# Mergen_Ground_Station_V2_0.net
KiCad netlist of a schematic drawn in EAGLE
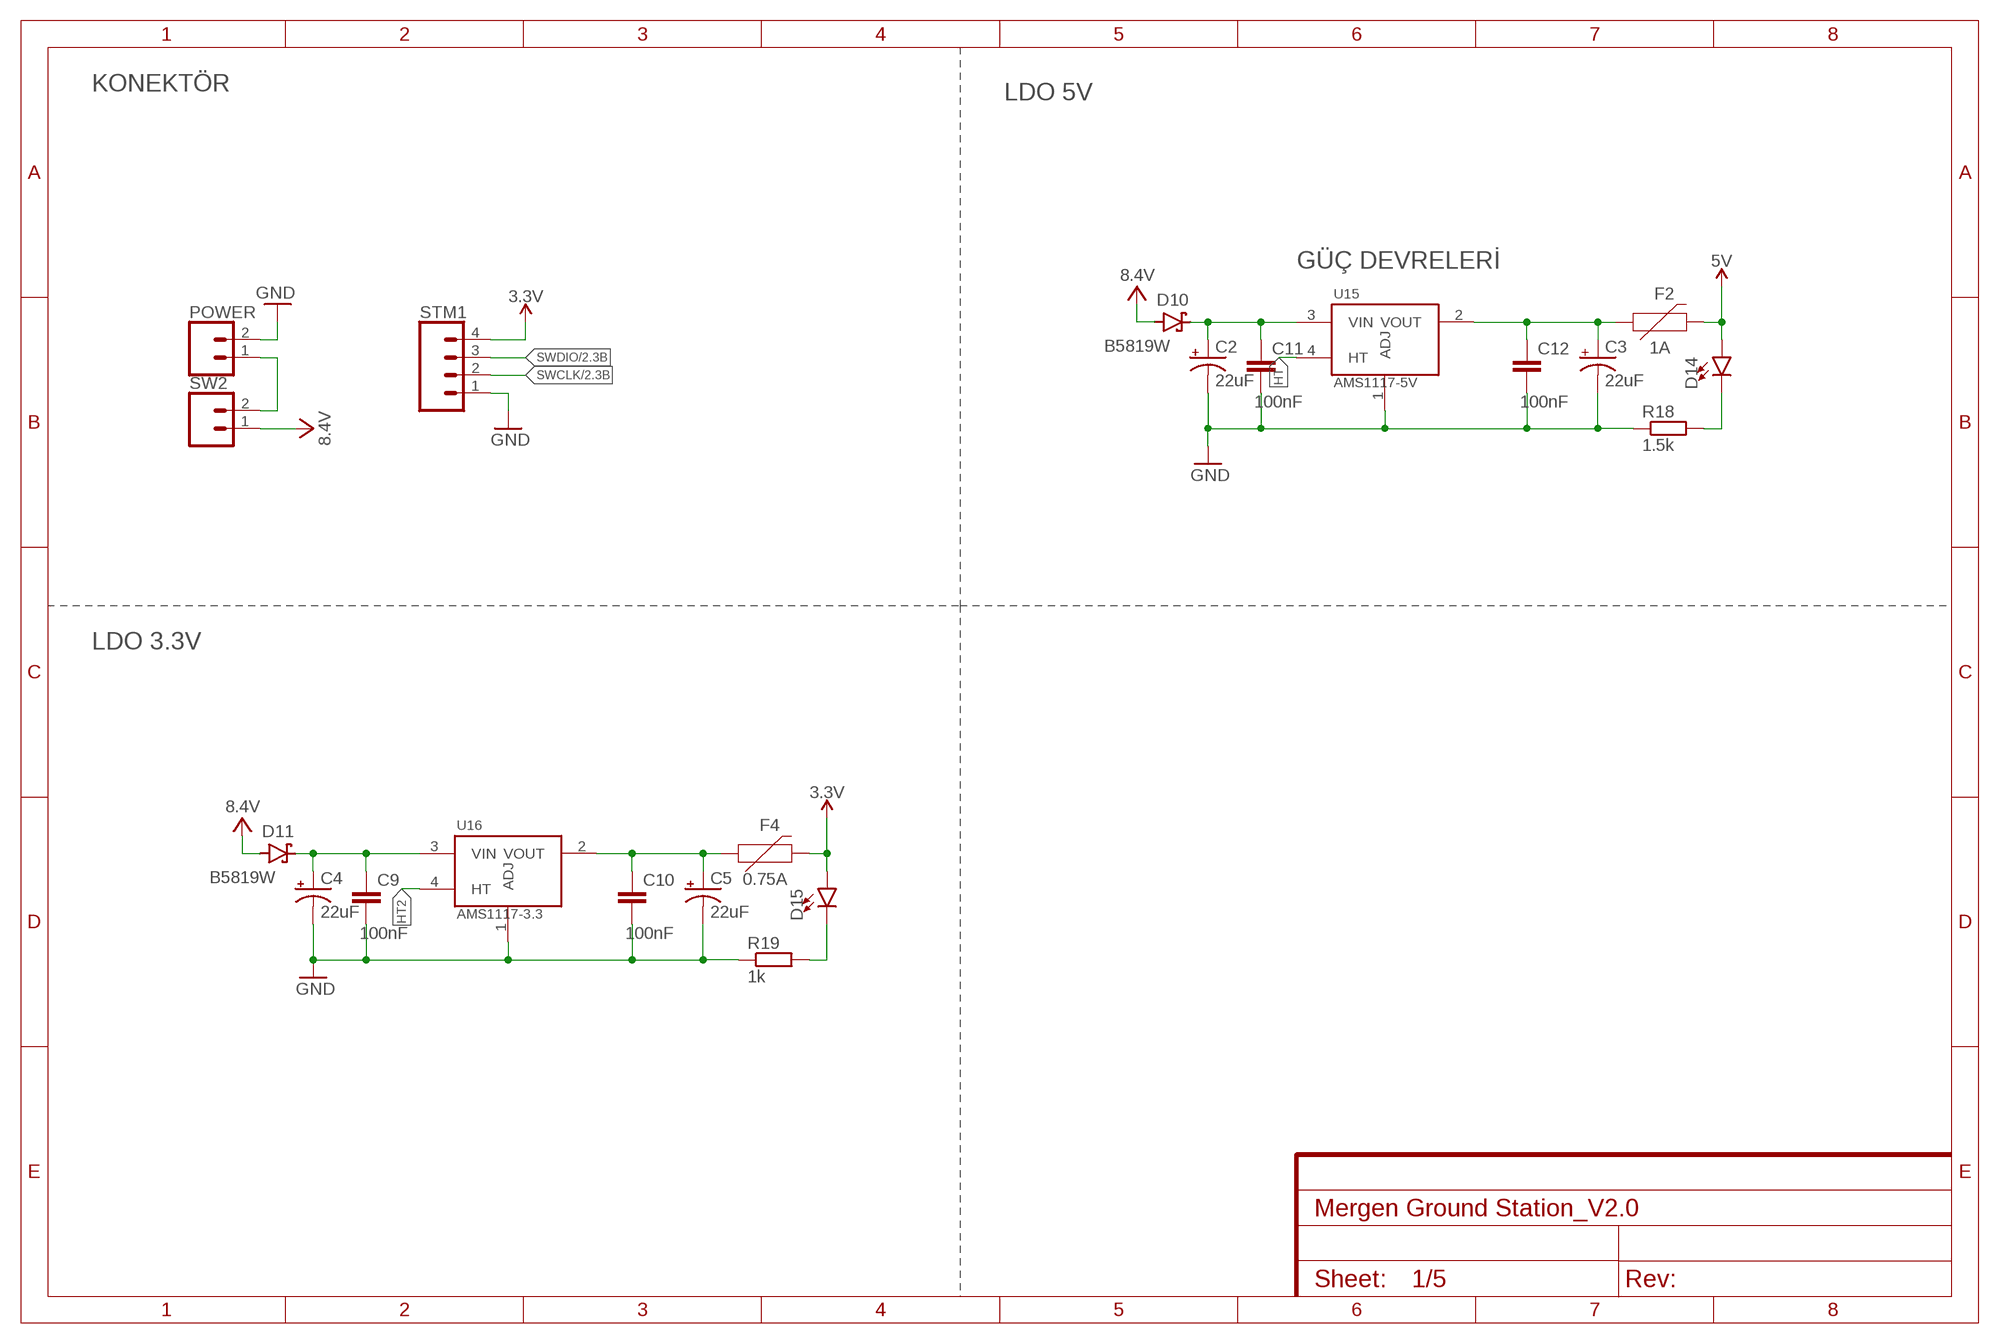
[diagram p0: schematic, sheet 1]
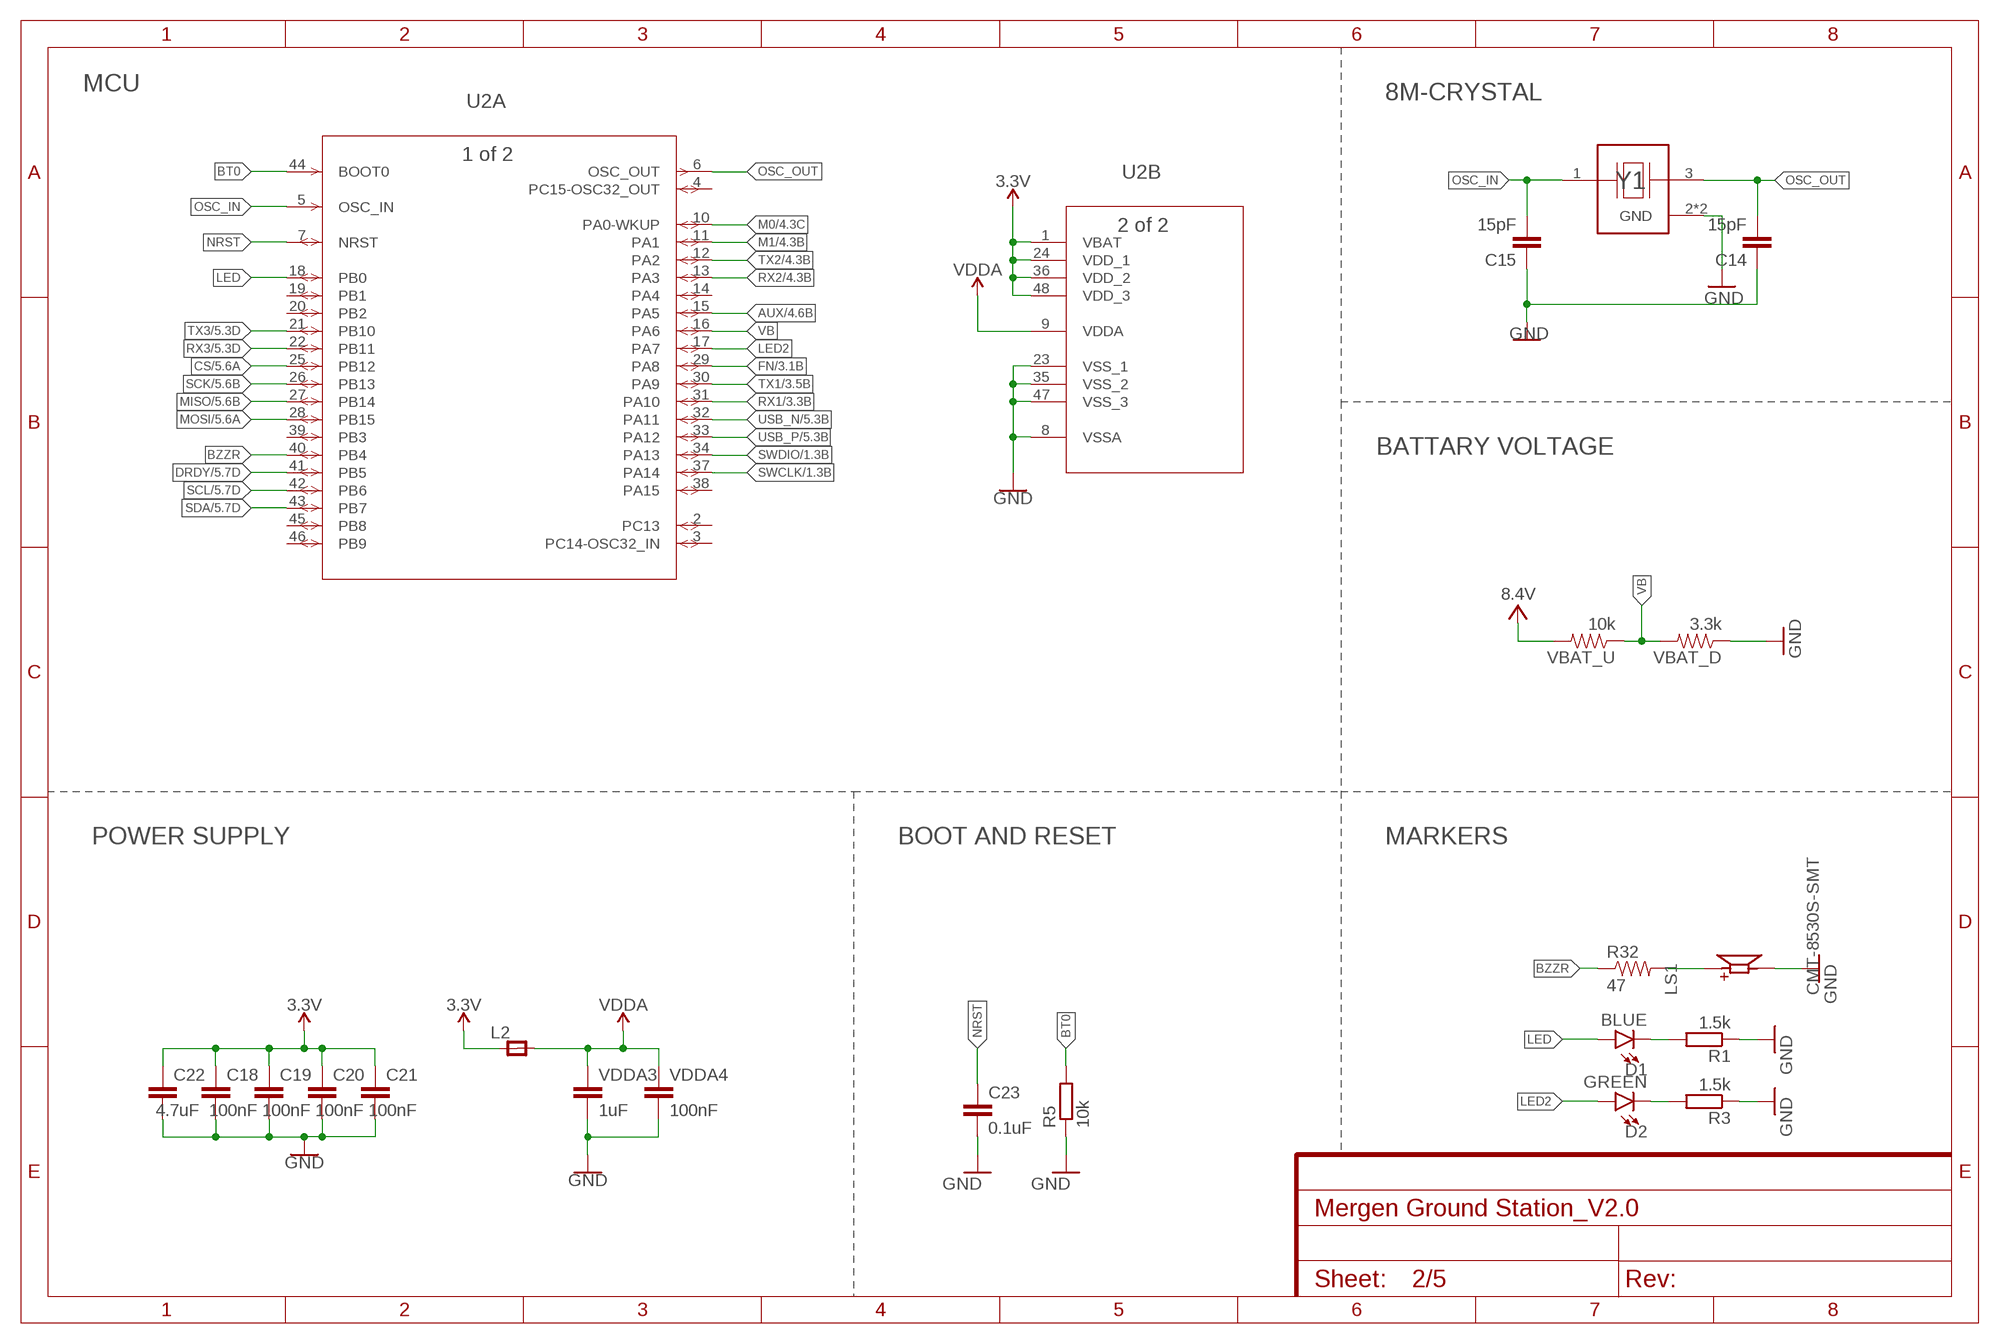
[diagram p1: schematic, sheet 2]
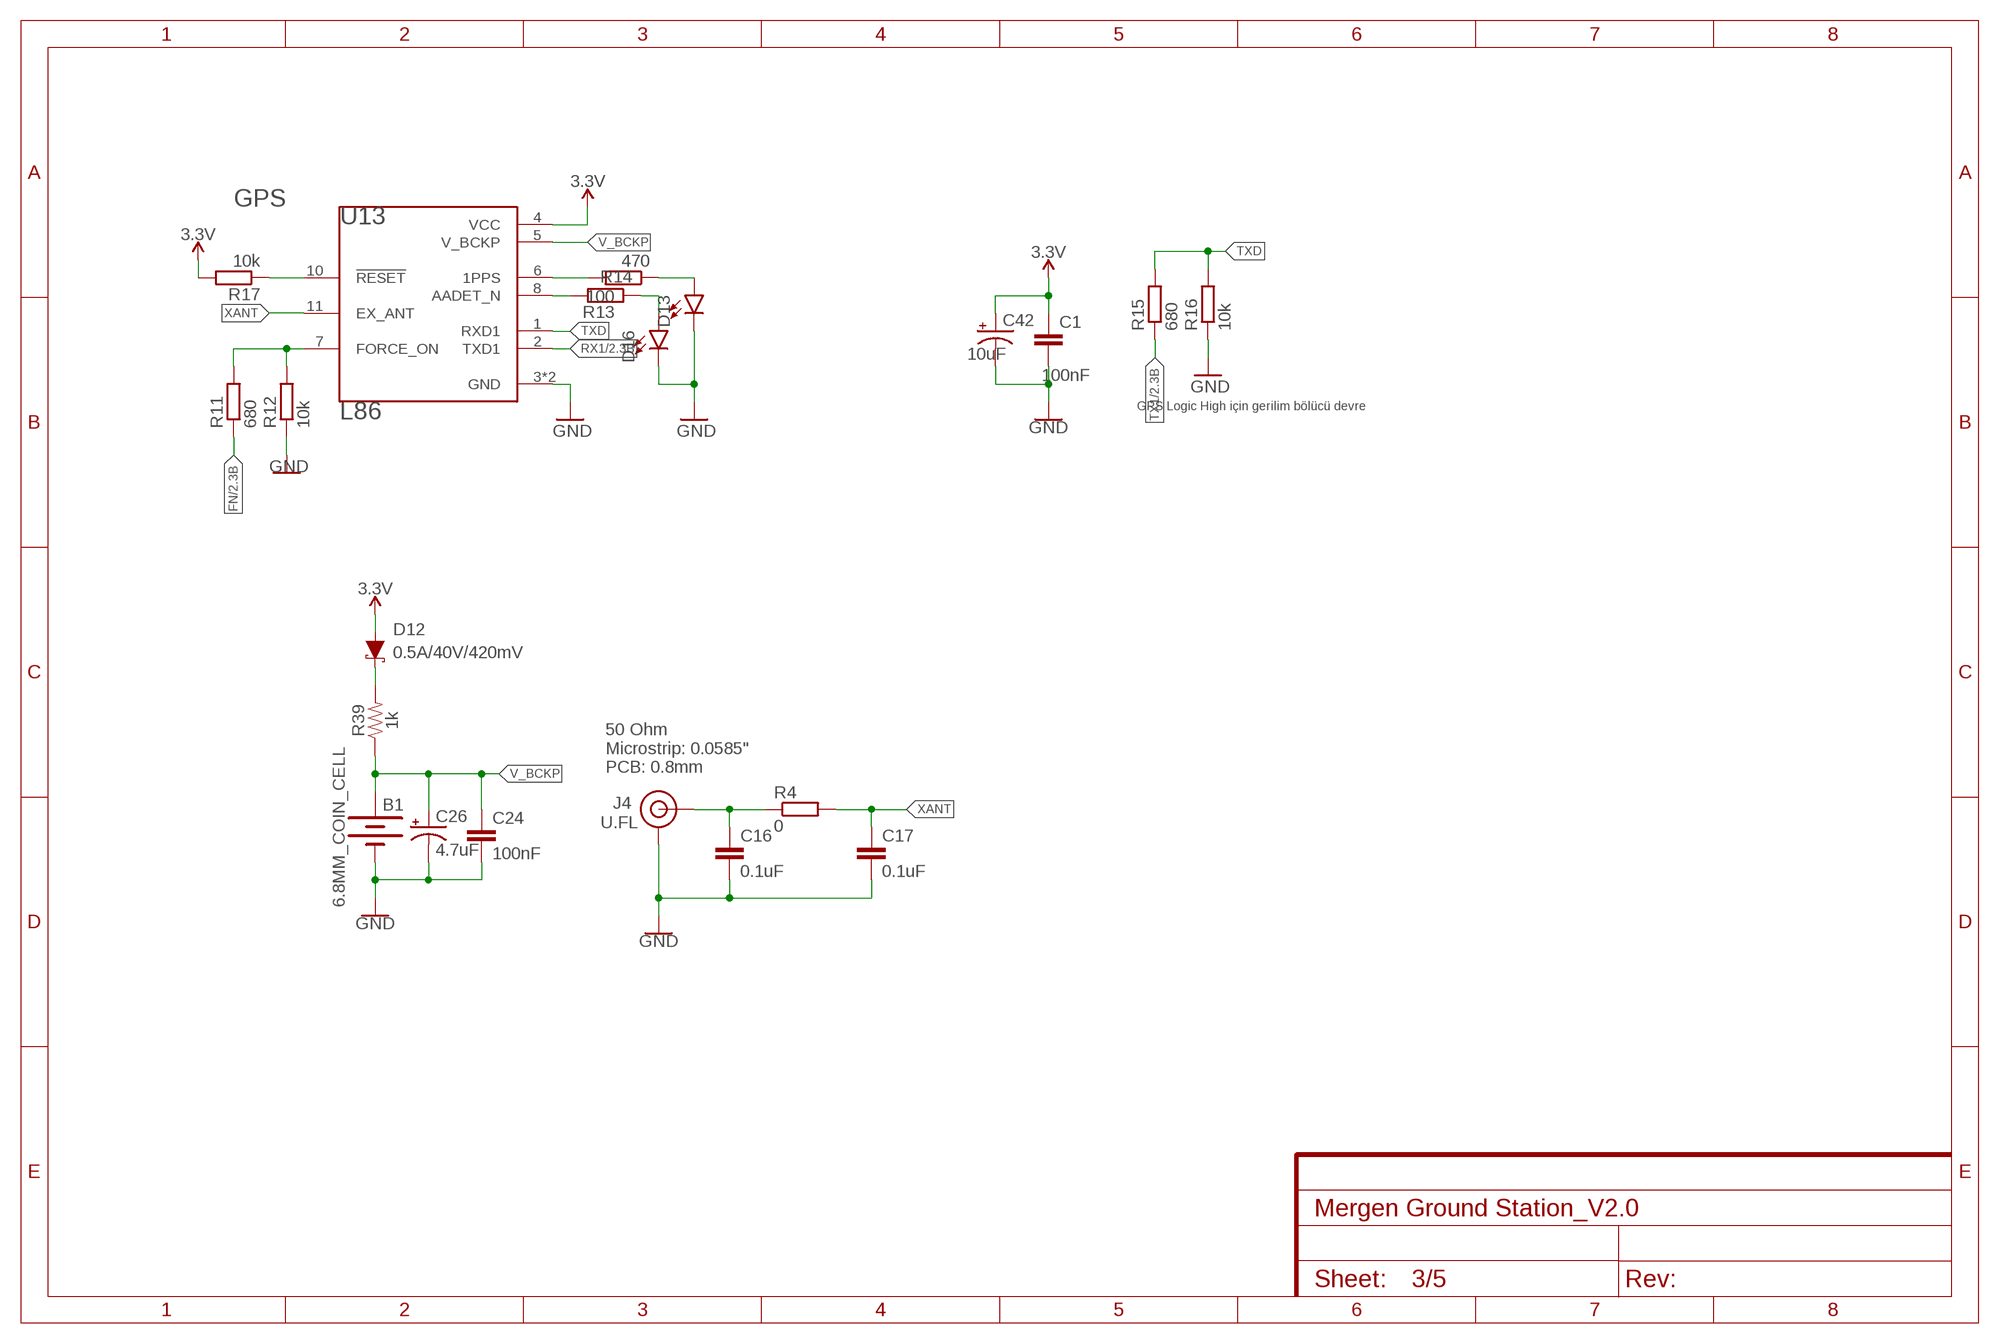
[diagram p2: schematic, sheet 3]
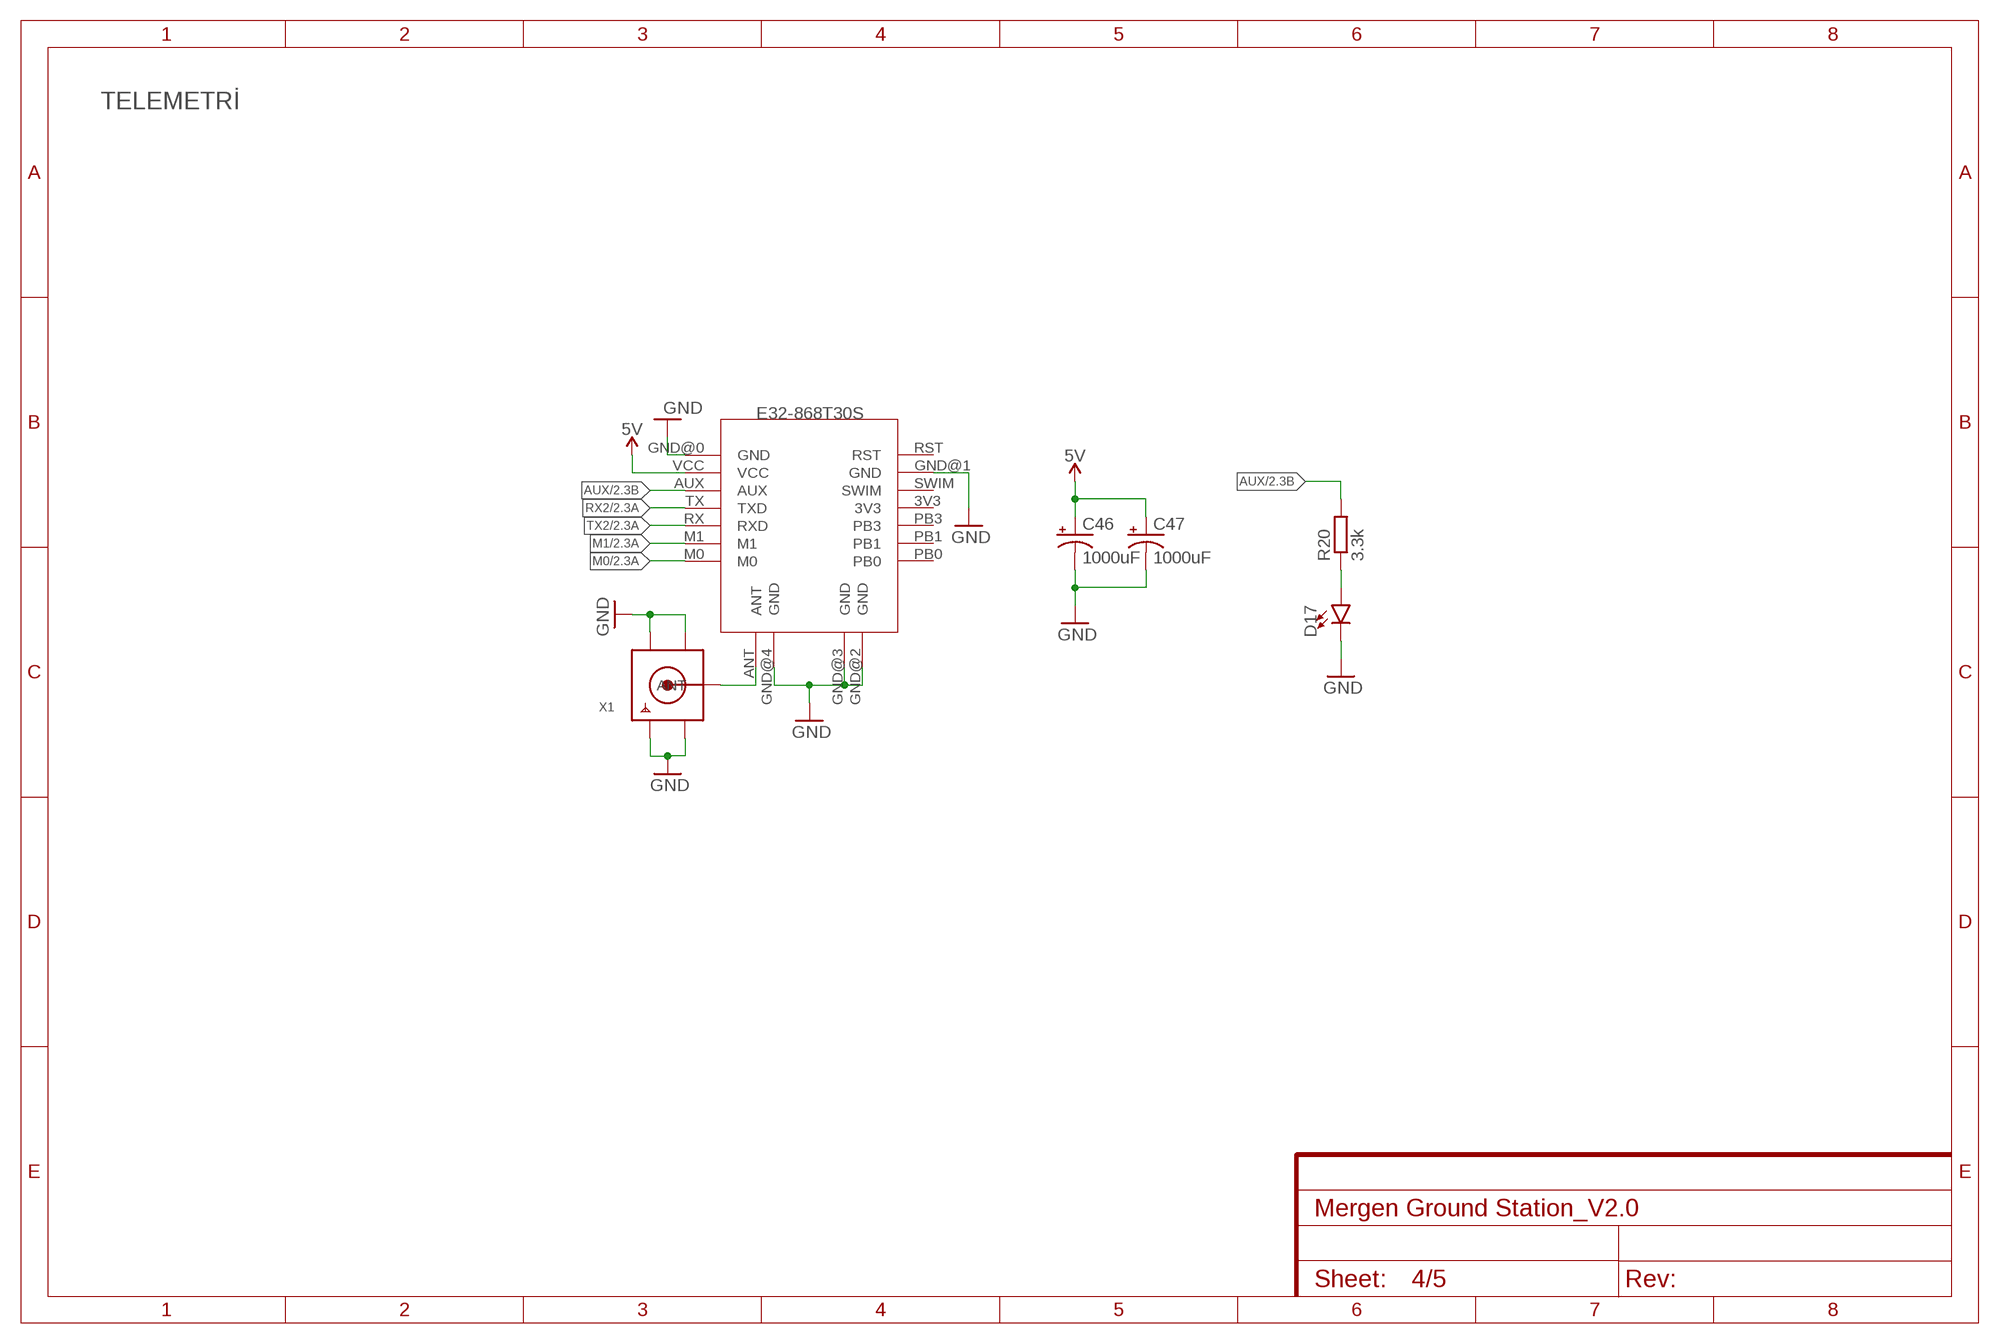
[diagram p3: schematic, sheet 4]
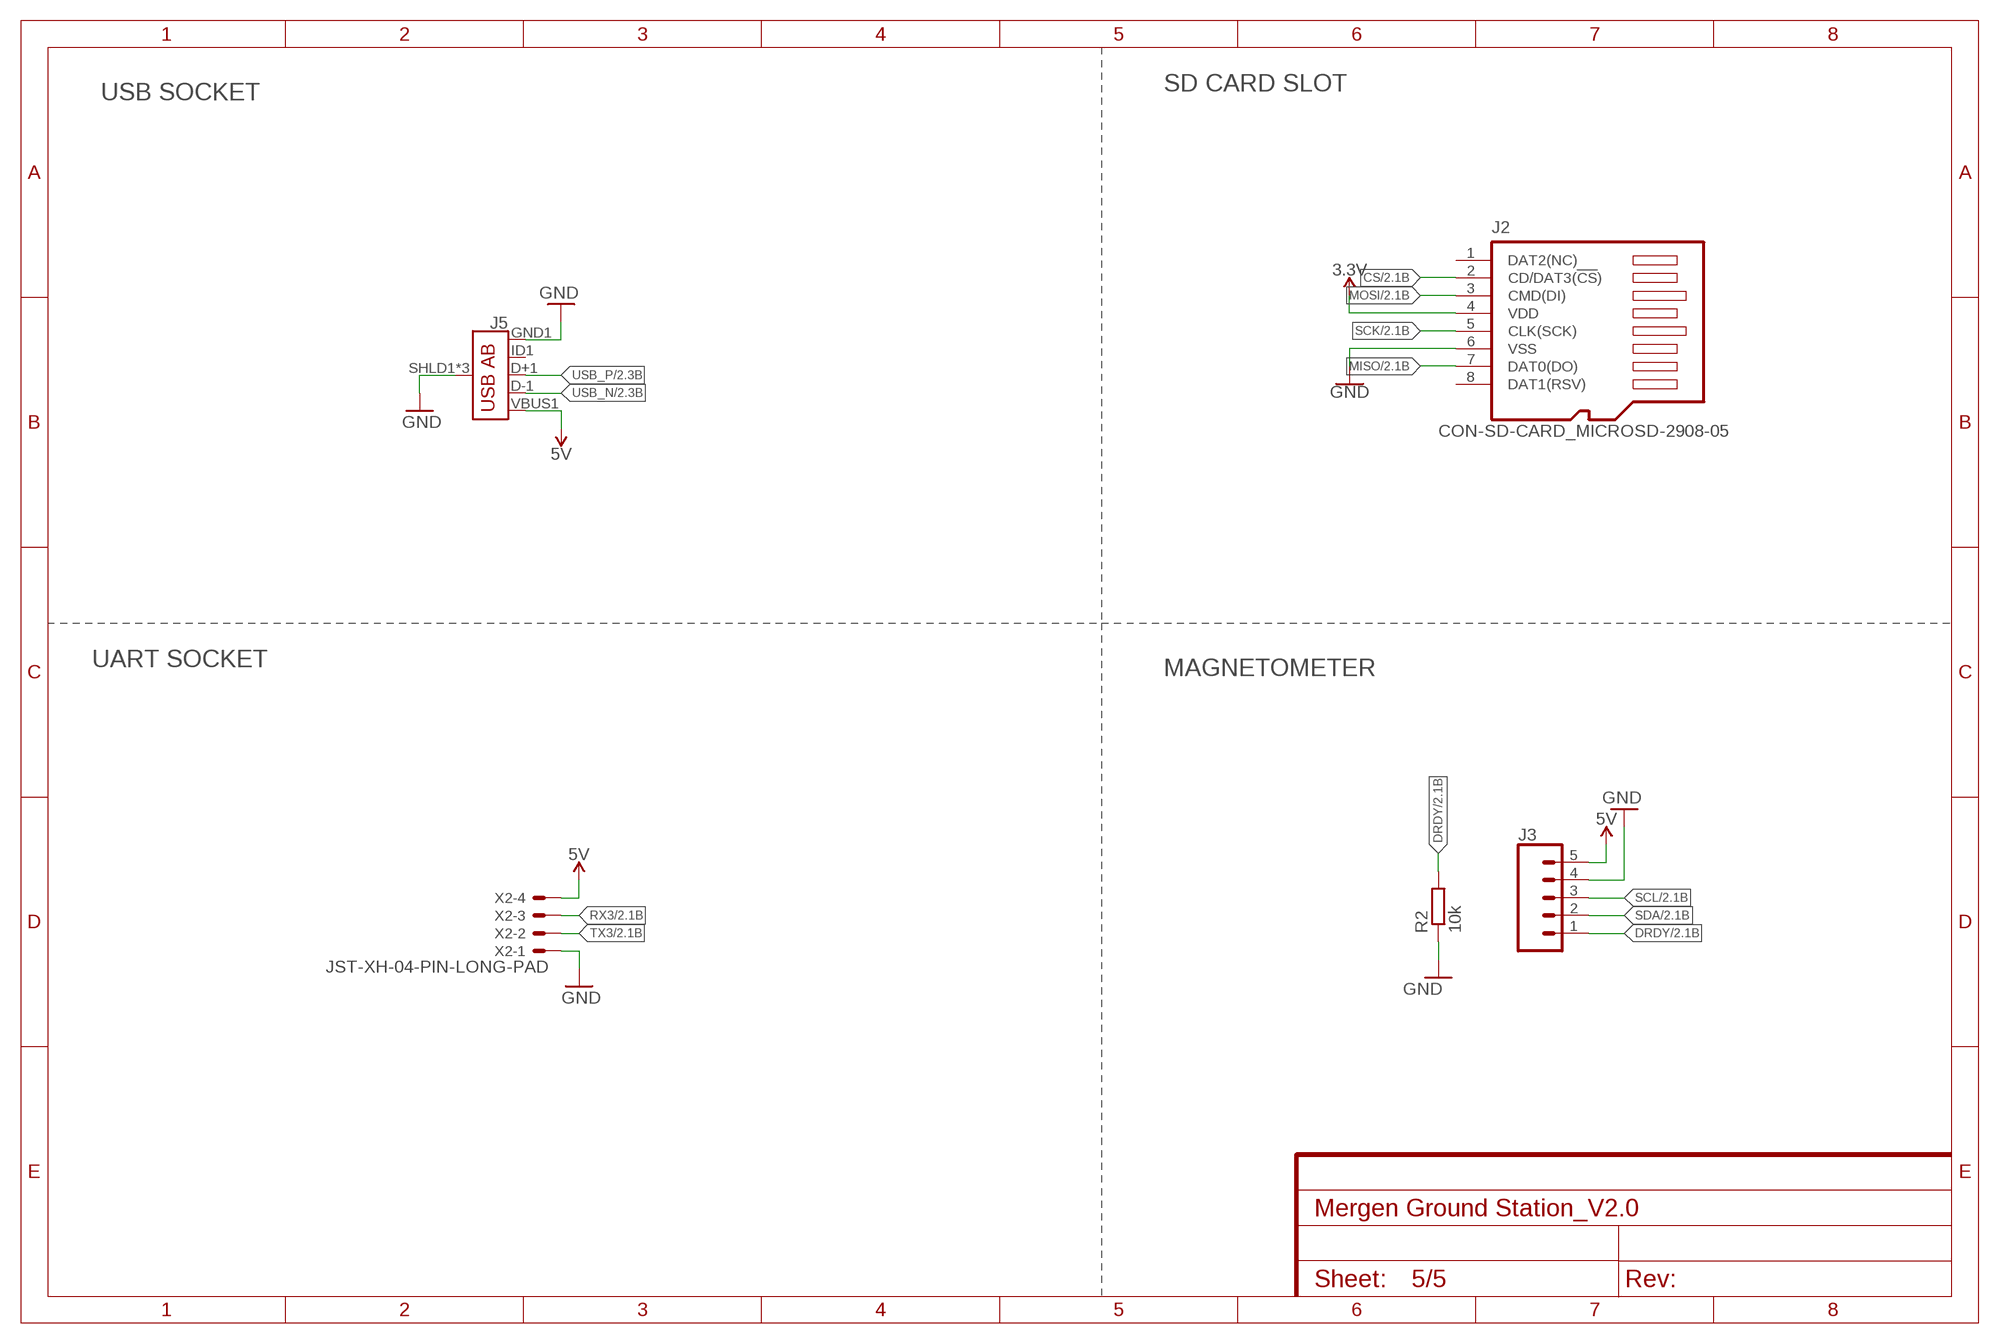
[diagram p4: schematic, sheet 5]

(export (version "E")
  (design (tool "Eeschema 10.0.6"))
  (components
    (comp (ref "C2")
      (value "22uF")
      (footprint "eagle-import:CT3528")
      (libsource (lib "eagle-import") (part "rcl_334_CPOL-USCT3528"))
    )
    (comp (ref "C3")
      (value "22uF")
      (footprint "eagle-import:CT3528")
      (libsource (lib "eagle-import") (part "rcl_334_CPOL-USCT3528"))
    )
    (comp (ref "C4")
      (value "22uF")
      (footprint "eagle-import:CT3528")
      (libsource (lib "eagle-import") (part "rcl_334_CPOL-USCT3528"))
    )
    (comp (ref "C5")
      (value "22uF")
      (footprint "eagle-import:CT3528")
      (libsource (lib "eagle-import") (part "rcl_334_CPOL-USCT3528"))
    )
    (comp (ref "C9")
      (value "100nF")
      (footprint "eagle-import:C0603")
      (libsource (lib "eagle-import") (part "C-EUC0603"))
    )
    (comp (ref "C10")
      (value "100nF")
      (footprint "eagle-import:C0603")
      (libsource (lib "eagle-import") (part "C-EUC0603"))
    )
    (comp (ref "C11")
      (value "100nF")
      (footprint "eagle-import:C0603")
      (libsource (lib "eagle-import") (part "C-EUC0603"))
    )
    (comp (ref "C12")
      (value "100nF")
      (footprint "eagle-import:C0603")
      (libsource (lib "eagle-import") (part "C-EUC0603"))
    )
    (comp (ref "D10")
      (value "B5819W")
      (footprint "eagle-import:SODFL3718X115")
      (fields (field (name "MANUFACTURER") "ON Semiconductor") (field (name "MPN") "MBR0520LT1G"))
      (libsource (lib "eagle-import") (part "SCHOTTKY_DO-219MBR0520LT1G"))
    )
    (comp (ref "D11")
      (value "B5819W")
      (footprint "eagle-import:SODFL3718X115")
      (fields (field (name "MANUFACTURER") "ON Semiconductor") (field (name "MPN") "MBR0520LT1G"))
      (libsource (lib "eagle-import") (part "SCHOTTKY_DO-219MBR0520LT1G"))
    )
    (comp (ref "D14")
      (value "LED0603")
      (footprint "eagle-import:LED-0603")
      (libsource (lib "eagle-import") (part "LED0603"))
    )
    (comp (ref "D15")
      (value "LED0603")
      (footprint "eagle-import:LED-0603")
      (libsource (lib "eagle-import") (part "LED0603"))
    )
    (comp (ref "F2")
      (value "1A")
      (footprint "eagle-import:1206")
      (libsource (lib "eagle-import") (part "PPTC_HALF-AMP"))
    )
    (comp (ref "F4")
      (value "0.75A")
      (footprint "eagle-import:1206")
      (libsource (lib "eagle-import") (part "PPTC_HALF-AMP"))
    )
    (comp (ref "POWER")
      (value "CONN_023.5MM-NO_SILK")
      (footprint "eagle-import:SCREWTERMINAL-3.5MM-2-NS")
      (libsource (lib "eagle-import") (part "CONN_023.5MM-NO_SILK"))
    )
    (comp (ref "R18")
      (value "1.5k")
      (footprint "eagle-import:R0603")
      (libsource (lib "eagle-import") (part "R-EU_R0603"))
    )
    (comp (ref "R19")
      (value "1k")
      (footprint "eagle-import:R0603")
      (libsource (lib "eagle-import") (part "R-EU_R0603"))
    )
    (comp (ref "STM1")
      (value "CONN_04")
      (footprint "eagle-import:1X04")
      (libsource (lib "eagle-import") (part "CONN_04"))
    )
    (comp (ref "SW2")
      (value "CONN_023.5MM-NO_SILK")
      (footprint "eagle-import:SCREWTERMINAL-3.5MM-2-NS")
      (libsource (lib "eagle-import") (part "CONN_023.5MM-NO_SILK"))
    )
    (comp (ref "U15")
      (value "AMS1117-5V")
      (footprint "eagle-import:SOT229P700X180-4N")
      (fields (field (name "MF") "Advanced Monolithic Systems") (field (name "MP") "AMS1117-3.3"))
      (libsource (lib "eagle-import") (part "AMS1117-3.3"))
    )
    (comp (ref "U16")
      (value "AMS1117-3.3")
      (footprint "eagle-import:SOT229P700X180-4N")
      (fields (field (name "MF") "Advanced Monolithic Systems"))
      (libsource (lib "eagle-import") (part "AMS1117-3.3"))
    )
    (comp (ref "C46")
      (value "1000uF")
      (footprint "eagle-import:150CLZ-1010")
      (libsource (lib "eagle-import") (part "CPOL-US150CLZ-1010"))
    )
    (comp (ref "C47")
      (value "1000uF")
      (footprint "eagle-import:150CLZ-1010")
      (libsource (lib "eagle-import") (part "CPOL-US150CLZ-1010"))
    )
    (comp (ref "D17")
      (value "LED0603")
      (footprint "eagle-import:LED-0603")
      (libsource (lib "eagle-import") (part "LED0603"))
    )
    (comp (ref "R20")
      (value "3.3k")
      (footprint "eagle-import:R0603")
      (libsource (lib "eagle-import") (part "R-EU_R0603"))
    )
    (comp (ref "U14")
      (value "E32-868T30S")
      (footprint "eagle-import:E32-868T30S")
      (libsource (lib "eagle-import") (part "E32-868T30S"))
    )
    (comp (ref "X1")
      (value "SMACONNECTOR")
      (footprint "eagle-import:SMA90_DIP")
      (libsource (lib "eagle-import") (part "SMACONNECTOR"))
    )
    (comp (ref "C14")
      (value "15pF")
      (footprint "eagle-import:C0603")
      (libsource (lib "eagle-import") (part "C-EUC0603"))
    )
    (comp (ref "C15")
      (value "15pF")
      (footprint "eagle-import:C0603")
      (libsource (lib "eagle-import") (part "C-EUC0603"))
    )
    (comp (ref "C18")
      (value "100nF")
      (footprint "eagle-import:C0603")
      (libsource (lib "eagle-import") (part "C-EUC0603"))
    )
    (comp (ref "C19")
      (value "100nF")
      (footprint "eagle-import:C0603")
      (libsource (lib "eagle-import") (part "C-EUC0603"))
    )
    (comp (ref "C20")
      (value "100nF")
      (footprint "eagle-import:C0603")
      (libsource (lib "eagle-import") (part "C-EUC0603"))
    )
    (comp (ref "C21")
      (value "100nF")
      (footprint "eagle-import:C0603")
      (libsource (lib "eagle-import") (part "C-EUC0603"))
    )
    (comp (ref "C22")
      (value "4.7uF")
      (footprint "eagle-import:C0603")
      (libsource (lib "eagle-import") (part "C-EUC0603"))
    )
    (comp (ref "C23")
      (value "0.1uF")
      (footprint "eagle-import:C0603")
      (libsource (lib "eagle-import") (part "C-EUC0603"))
    )
    (comp (ref "D1")
      (value "BLUE")
      (footprint "eagle-import:LED-0603")
      (libsource (lib "eagle-import") (part "LED0603"))
    )
    (comp (ref "D2")
      (value "GREEN")
      (footprint "eagle-import:LED-0603")
      (libsource (lib "eagle-import") (part "LED0603"))
    )
    (comp (ref "L2")
      (value "RC-MASTER-SMD_FB_0805MP")
      (footprint "eagle-import:RC-MASTER-SMD_L0805MP")
      (libsource (lib "eagle-import") (part "RC-MASTER-SMD_FB_0805MP"))
    )
    (comp (ref "LS1")
      (value "CMT-8530S-SMT")
      (footprint "eagle-import:CUI_CMT-8530S-SMT")
      (fields (field (name "MF") "CUI Devices") (field (name "MP") "CMT-8530S-SMT-TR"))
      (libsource (lib "eagle-import") (part "CMT-8530S-SMT"))
    )
    (comp (ref "R1")
      (value "1.5k")
      (footprint "eagle-import:R0603")
      (libsource (lib "eagle-import") (part "R-EU_R0603"))
    )
    (comp (ref "R3")
      (value "1.5k")
      (footprint "eagle-import:R0603")
      (libsource (lib "eagle-import") (part "R-EU_R0603"))
    )
    (comp (ref "R5")
      (value "10k")
      (footprint "eagle-import:R0603")
      (libsource (lib "eagle-import") (part "R-EU_R0603"))
    )
    (comp (ref "R32")
      (value "47")
      (footprint "eagle-import:0603")
      (libsource (lib "eagle-import") (part "0OHM-0603-1/10W-5%"))
    )
    (comp (ref "U2")
      (value "STM32F103C8T6")
      (footprint "eagle-import:LQFP48-7X7MM")
      (fields (field (name "COPYRIGHT") "Copyright (C) 2018 Accelerated Designs. All rights reserved"))
      (libsource (lib "eagle-import") (part "STM32F103C8T6"))
    )
    (comp (ref "VBAT_D")
      (value "3.3k")
      (footprint "eagle-import:0603-RES")
      (libsource (lib "eagle-import") (part "2.0KOHM1/10W5%(0603)"))
    )
    (comp (ref "VBAT_U")
      (value "10k")
      (footprint "eagle-import:0603-RES")
      (libsource (lib "eagle-import") (part "2.0KOHM1/10W5%(0603)"))
    )
    (comp (ref "VDDA3")
      (value "1uF")
      (footprint "eagle-import:0603")
      (libsource (lib "eagle-import") (part "0.1UF-0603-25V-(+80/-20%)"))
    )
    (comp (ref "VDDA4")
      (value "100nF")
      (footprint "eagle-import:0603")
      (libsource (lib "eagle-import") (part "0.1UF-0603-25V-(+80/-20%)"))
    )
    (comp (ref "Y1")
      (value "ABMM2-8.000MHZ-E2-T")
      (footprint "eagle-import:XTAL_ABMM2-8.000MHZ-E2-T")
      (fields (field (name "MF") "Abracon"))
      (libsource (lib "eagle-import") (part "ABMM2-8.000MHZ-E2-T"))
    )
    (comp (ref "J2")
      (value "CON-SD-CARD_MICROSD-2908-05")
      (footprint "eagle-import:CON-SD-CARD_2908-05")
      (libsource (lib "eagle-import") (part "CON-SD-CARD_MICROSD-2908-05"))
    )
    (comp (ref "J3")
      (value "CONN_05LOCK_LONGPADS")
      (footprint "eagle-import:1X05_LOCK_LONGPADS")
      (libsource (lib "eagle-import") (part "CONN_05LOCK_LONGPADS"))
    )
    (comp (ref "J5")
      (value "USB_AB_SMT")
      (footprint "eagle-import:USB-AB-MICRO-SMD")
      (libsource (lib "eagle-import") (part "USB_AB_SMT"))
    )
    (comp (ref "R2")
      (value "10k")
      (footprint "eagle-import:R0603")
      (libsource (lib "eagle-import") (part "R-EU_R0603"))
    )
    (comp (ref "X2")
      (value "JST-XH-04-PIN-LONG-PAD")
      (footprint "eagle-import:JST-XH-04-PACKAGE-LONG-PAD")
      (libsource (lib "eagle-import") (part "JST-XH-04-PIN-LONG-PAD"))
    )
    (comp (ref "B1")
      (value "6.8MM_COIN_CELL")
      (footprint "eagle-import:BATTCON-6.8MM")
      (libsource (lib "eagle-import") (part "BATTERY-6.8MM_SMD"))
    )
    (comp (ref "C1")
      (value "100nF")
      (footprint "eagle-import:C0603")
      (libsource (lib "eagle-import") (part "C-EUC0603"))
    )
    (comp (ref "C16")
      (value "0.1uF")
      (footprint "eagle-import:C0603")
      (libsource (lib "eagle-import") (part "C-EUC0603"))
    )
    (comp (ref "C17")
      (value "0.1uF")
      (footprint "eagle-import:C0603")
      (libsource (lib "eagle-import") (part "C-EUC0603"))
    )
    (comp (ref "C24")
      (value "100nF")
      (footprint "eagle-import:C0603")
      (libsource (lib "eagle-import") (part "C-EUC0603"))
    )
    (comp (ref "C26")
      (value "4.7uF")
      (footprint "eagle-import:A_3216-18R")
      (libsource (lib "eagle-import") (part "rcl_334_CPOL-USA/3216-18R"))
    )
    (comp (ref "C42")
      (value "10uF")
      (footprint "eagle-import:EIA3216")
      (libsource (lib "eagle-import") (part "10UF-POLAR-EIA3216-16V-10%(TANT)"))
    )
    (comp (ref "D12")
      (value "0.5A/40V/420mV")
      (footprint "eagle-import:SOD-323")
      (libsource (lib "eagle-import") (part "DIODE-SCHOTTKY-PMEG4005EJ"))
    )
    (comp (ref "D13")
      (value "LED0603")
      (footprint "eagle-import:LED-0603")
      (libsource (lib "eagle-import") (part "LED0603"))
    )
    (comp (ref "D16")
      (value "LED0603")
      (footprint "eagle-import:LED-0603")
      (libsource (lib "eagle-import") (part "LED0603"))
    )
    (comp (ref "J4")
      (value "U.FL")
      (footprint "eagle-import:U.FL")
      (libsource (lib "eagle-import") (part "U.FL2PIN"))
    )
    (comp (ref "R4")
      (value "0")
      (footprint "eagle-import:R0603")
      (libsource (lib "eagle-import") (part "R-EU_R0603"))
    )
    (comp (ref "R11")
      (value "680")
      (footprint "eagle-import:R0603")
      (libsource (lib "eagle-import") (part "R-EU_R0603"))
    )
    (comp (ref "R12")
      (value "10k")
      (footprint "eagle-import:R0603")
      (libsource (lib "eagle-import") (part "R-EU_R0603"))
    )
    (comp (ref "R13")
      (value "100")
      (footprint "eagle-import:R0603")
      (libsource (lib "eagle-import") (part "R-EU_R0603"))
    )
    (comp (ref "R14")
      (value "470")
      (footprint "eagle-import:R0603")
      (libsource (lib "eagle-import") (part "R-EU_R0603"))
    )
    (comp (ref "R15")
      (value "680")
      (footprint "eagle-import:R0603")
      (libsource (lib "eagle-import") (part "R-EU_R0603"))
    )
    (comp (ref "R16")
      (value "10k")
      (footprint "eagle-import:R0603")
      (libsource (lib "eagle-import") (part "R-EU_R0603"))
    )
    (comp (ref "R17")
      (value "10k")
      (footprint "eagle-import:R0603")
      (libsource (lib "eagle-import") (part "R-EU_R0603"))
    )
    (comp (ref "R39")
      (value "1k")
      (footprint "eagle-import:0603")
      (libsource (lib "eagle-import") (part "1KOHM-0603-1/10W-1%"))
    )
    (comp (ref "U13")
      (value "L86")
      (footprint "eagle-import:XCVR_L86")
      (fields (field (name "MF") "Quectel"))
      (libsource (lib "eagle-import") (part "L86"))
    )
  )
  (nets
    (net (code "1") (name "3.3V") (class "Default")
      (node (ref "C1") (pin "1") (pinfunction "1_1") (pintype "passive"))
      (node (ref "C18") (pin "1") (pinfunction "1_1") (pintype "passive"))
      (node (ref "C19") (pin "1") (pinfunction "1_1") (pintype "passive"))
      (node (ref "C20") (pin "1") (pinfunction "1_1") (pintype "passive"))
      (node (ref "C21") (pin "1") (pinfunction "1_1") (pintype "passive"))
      (node (ref "C22") (pin "1") (pinfunction "1_1") (pintype "passive"))
      (node (ref "C42") (pin "+") (pinfunction "+_+") (pintype "passive"))
      (node (ref "D12") (pin "A") (pinfunction "A_A") (pintype "passive"))
      (node (ref "D15") (pin "A") (pinfunction "A_A") (pintype "passive"))
      (node (ref "F4") (pin "2") (pinfunction "2_2") (pintype "bidirectional"))
      (node (ref "J2") (pin "4") (pinfunction "VDD_4") (pintype "bidirectional"))
      (node (ref "L2") (pin "1") (pinfunction "1_1") (pintype "passive"))
      (node (ref "R17") (pin "2") (pinfunction "2_2") (pintype "passive"))
      (node (ref "STM1") (pin "4") (pinfunction "4_4") (pintype "passive"))
      (node (ref "U13") (pin "4") (pinfunction "VCC_4") (pintype "power_in"))
      (node (ref "U2") (pin "1") (pinfunction "VBAT_1") (pintype "power_in"))
      (node (ref "U2") (pin "24") (pinfunction "VDD_1_24") (pintype "power_in"))
      (node (ref "U2") (pin "36") (pinfunction "VDD_2_36") (pintype "power_in"))
      (node (ref "U2") (pin "48") (pinfunction "VDD_3_48") (pintype "power_in"))
    )
    (net (code "2") (name "5V") (class "Default")
      (node (ref "C46") (pin "+") (pinfunction "+_+") (pintype "passive"))
      (node (ref "C47") (pin "+") (pinfunction "+_+") (pintype "passive"))
      (node (ref "D14") (pin "A") (pinfunction "A_A") (pintype "passive"))
      (node (ref "F2") (pin "2") (pinfunction "2_2") (pintype "bidirectional"))
      (node (ref "J3") (pin "5") (pinfunction "5_5") (pintype "passive"))
      (node (ref "J5") (pin "VBUS1") (pinfunction "VBUS_VBUS1") (pintype "power_in"))
      (node (ref "U14") (pin "VCC") (pinfunction "VCC_VCC") (pintype "bidirectional"))
      (node (ref "X2") (pin "4") (pinfunction "S_4") (pintype "passive"))
    )
    (net (code "3") (name "AUX") (class "Default")
      (node (ref "R20") (pin "2") (pinfunction "2_2") (pintype "passive"))
      (node (ref "U14") (pin "AUX") (pinfunction "AUX_AUX") (pintype "bidirectional"))
      (node (ref "U2") (pin "15") (pinfunction "PA5_15") (pintype "bidirectional"))
    )
    (net (code "4") (name "BT0") (class "Default")
      (node (ref "R5") (pin "2") (pinfunction "2_2") (pintype "passive"))
      (node (ref "U2") (pin "44") (pinfunction "BOOT0_44") (pintype "input"))
    )
    (net (code "5") (name "BZZR") (class "Default")
      (node (ref "R32") (pin "1") (pinfunction "1_1") (pintype "passive"))
      (node (ref "U2") (pin "40") (pinfunction "PB4_40") (pintype "bidirectional"))
    )
    (net (code "6") (name "CS") (class "Default")
      (node (ref "J2") (pin "2") (pinfunction "CD/DAT3(~{CS})_2") (pintype "bidirectional"))
      (node (ref "U2") (pin "25") (pinfunction "PB12_25") (pintype "bidirectional"))
    )
    (net (code "7") (name "DRDY") (class "Default")
      (node (ref "J3") (pin "1") (pinfunction "1_1") (pintype "passive"))
      (node (ref "R2") (pin "2") (pinfunction "2_2") (pintype "passive"))
      (node (ref "U2") (pin "41") (pinfunction "PB5_41") (pintype "bidirectional"))
    )
    (net (code "8") (name "FN") (class "Default")
      (node (ref "R11") (pin "1") (pinfunction "1_1") (pintype "passive"))
      (node (ref "U2") (pin "29") (pinfunction "PA8_29") (pintype "bidirectional"))
    )
    (net (code "9") (name "GND") (class "Default")
      (node (ref "B1") (pin "-") (pinfunction "-_-") (pintype "power_in"))
      (node (ref "C1") (pin "2") (pinfunction "2_2") (pintype "passive"))
      (node (ref "C10") (pin "2") (pinfunction "2_2") (pintype "passive"))
      (node (ref "C11") (pin "2") (pinfunction "2_2") (pintype "passive"))
      (node (ref "C12") (pin "2") (pinfunction "2_2") (pintype "passive"))
      (node (ref "C14") (pin "1") (pinfunction "1_1") (pintype "passive"))
      (node (ref "C15") (pin "1") (pinfunction "1_1") (pintype "passive"))
      (node (ref "C16") (pin "2") (pinfunction "2_2") (pintype "passive"))
      (node (ref "C17") (pin "2") (pinfunction "2_2") (pintype "passive"))
      (node (ref "C18") (pin "2") (pinfunction "2_2") (pintype "passive"))
      (node (ref "C19") (pin "2") (pinfunction "2_2") (pintype "passive"))
      (node (ref "C2") (pin "-") (pinfunction "-_-") (pintype "passive"))
      (node (ref "C20") (pin "2") (pinfunction "2_2") (pintype "passive"))
      (node (ref "C21") (pin "2") (pinfunction "2_2") (pintype "passive"))
      (node (ref "C22") (pin "2") (pinfunction "2_2") (pintype "passive"))
      (node (ref "C23") (pin "2") (pinfunction "2_2") (pintype "passive"))
      (node (ref "C24") (pin "2") (pinfunction "2_2") (pintype "passive"))
      (node (ref "C26") (pin "-") (pinfunction "-_-") (pintype "passive"))
      (node (ref "C3") (pin "-") (pinfunction "-_-") (pintype "passive"))
      (node (ref "C4") (pin "-") (pinfunction "-_-") (pintype "passive"))
      (node (ref "C42") (pin "-") (pinfunction "-_-") (pintype "passive"))
      (node (ref "C46") (pin "-") (pinfunction "-_-") (pintype "passive"))
      (node (ref "C47") (pin "-") (pinfunction "-_-") (pintype "passive"))
      (node (ref "C5") (pin "-") (pinfunction "-_-") (pintype "passive"))
      (node (ref "C9") (pin "2") (pinfunction "2_2") (pintype "passive"))
      (node (ref "D13") (pin "C") (pinfunction "C_C") (pintype "passive"))
      (node (ref "D16") (pin "C") (pinfunction "C_C") (pintype "passive"))
      (node (ref "D17") (pin "C") (pinfunction "C_C") (pintype "passive"))
      (node (ref "J2") (pin "6") (pinfunction "VSS_6") (pintype "bidirectional"))
      (node (ref "J3") (pin "4") (pinfunction "4_4") (pintype "passive"))
      (node (ref "J4") (pin "1") (pinfunction "GND_1") (pintype "bidirectional"))
      (node (ref "J4") (pin "2") (pinfunction "GND_2") (pintype "bidirectional"))
      (node (ref "J5") (pin "GND1") (pinfunction "GND_GND1") (pintype "power_in"))
      (node (ref "J5") (pin "SHLD1") (pinfunction "SHIELD_SHLD1") (pintype "bidirectional"))
      (node (ref "J5") (pin "SHLD2") (pinfunction "SHIELD_SHLD2") (pintype "bidirectional"))
      (node (ref "J5") (pin "SHLD3") (pinfunction "SHIELD_SHLD3") (pintype "bidirectional"))
      (node (ref "LS1") (pin "N") (pinfunction "N_N") (pintype "passive"))
      (node (ref "POWER") (pin "2") (pinfunction "2_2") (pintype "passive"))
      (node (ref "R1") (pin "1") (pinfunction "1_1") (pintype "passive"))
      (node (ref "R12") (pin "1") (pinfunction "1_1") (pintype "passive"))
      (node (ref "R16") (pin "1") (pinfunction "1_1") (pintype "passive"))
      (node (ref "R18") (pin "1") (pinfunction "1_1") (pintype "passive"))
      (node (ref "R19") (pin "1") (pinfunction "1_1") (pintype "passive"))
      (node (ref "R2") (pin "1") (pinfunction "1_1") (pintype "passive"))
      (node (ref "R3") (pin "1") (pinfunction "1_1") (pintype "passive"))
      (node (ref "R5") (pin "1") (pinfunction "1_1") (pintype "passive"))
      (node (ref "STM1") (pin "1") (pinfunction "1_1") (pintype "passive"))
      (node (ref "U13") (pin "12") (pinfunction "GND_12") (pintype "passive"))
      (node (ref "U13") (pin "3") (pinfunction "GND_3") (pintype "passive"))
      (node (ref "U14") (pin "GND@0") (pinfunction "GND_GND@0") (pintype "bidirectional"))
      (node (ref "U14") (pin "GND@1") (pinfunction "GND_GND@1") (pintype "bidirectional"))
      (node (ref "U14") (pin "GND@2") (pinfunction "GND_GND@2") (pintype "bidirectional"))
      (node (ref "U14") (pin "GND@3") (pinfunction "GND_GND@3") (pintype "bidirectional"))
      (node (ref "U14") (pin "GND@4") (pinfunction "GND_GND@4") (pintype "bidirectional"))
      (node (ref "U15") (pin "1") (pinfunction "ADJ_1") (pintype "power_in"))
      (node (ref "U16") (pin "1") (pinfunction "ADJ_1") (pintype "power_in"))
      (node (ref "U2") (pin "23") (pinfunction "VSS_1_23") (pintype "power_in"))
      (node (ref "U2") (pin "35") (pinfunction "VSS_2_35") (pintype "power_in"))
      (node (ref "U2") (pin "47") (pinfunction "VSS_3_47") (pintype "power_in"))
      (node (ref "U2") (pin "8") (pinfunction "VSSA_8") (pintype "power_in"))
      (node (ref "VBAT_D") (pin "1") (pinfunction "1_1") (pintype "passive"))
      (node (ref "VDDA3") (pin "2") (pinfunction "2_2") (pintype "passive"))
      (node (ref "VDDA4") (pin "2") (pinfunction "2_2") (pintype "passive"))
      (node (ref "X1") (pin "GND1") (pinfunction "GND1_GND1") (pintype "power_in"))
      (node (ref "X1") (pin "GND2") (pinfunction "GND2_GND2") (pintype "power_in"))
      (node (ref "X1") (pin "GND3") (pinfunction "GND3_GND3") (pintype "power_in"))
      (node (ref "X1") (pin "GND4") (pinfunction "GND4_GND4") (pintype "power_in"))
      (node (ref "X2") (pin "1") (pinfunction "S_1") (pintype "passive"))
      (node (ref "Y1") (pin "2") (pinfunction "GND_2") (pintype "power_in"))
      (node (ref "Y1") (pin "4") (pinfunction "GND_4") (pintype "power_in"))
    )
    (net (code "10") (name "HT") (class "Default")
      (node (ref "U15") (pin "4") (pinfunction "HT_4") (pintype "bidirectional"))
    )
    (net (code "11") (name "HT2") (class "Default")
      (node (ref "U16") (pin "4") (pinfunction "HT_4") (pintype "bidirectional"))
    )
    (net (code "12") (name "LED") (class "Default")
      (node (ref "D1") (pin "A") (pinfunction "A_A") (pintype "passive"))
      (node (ref "U2") (pin "18") (pinfunction "PB0_18") (pintype "bidirectional"))
    )
    (net (code "13") (name "LED2") (class "Default")
      (node (ref "D2") (pin "A") (pinfunction "A_A") (pintype "passive"))
      (node (ref "U2") (pin "17") (pinfunction "PA7_17") (pintype "bidirectional"))
    )
    (net (code "14") (name "M0") (class "Default")
      (node (ref "U14") (pin "M0") (pinfunction "M0_M0") (pintype "bidirectional"))
      (node (ref "U2") (pin "10") (pinfunction "PA0-WKUP_10") (pintype "bidirectional"))
    )
    (net (code "15") (name "M1") (class "Default")
      (node (ref "U14") (pin "M1") (pinfunction "M1_M1") (pintype "bidirectional"))
      (node (ref "U2") (pin "11") (pinfunction "PA1_11") (pintype "bidirectional"))
    )
    (net (code "16") (name "MISO") (class "Default")
      (node (ref "J2") (pin "7") (pinfunction "DAT0(DO)_7") (pintype "bidirectional"))
      (node (ref "U2") (pin "27") (pinfunction "PB14_27") (pintype "bidirectional"))
    )
    (net (code "17") (name "MOSI") (class "Default")
      (node (ref "J2") (pin "3") (pinfunction "CMD(DI)_3") (pintype "bidirectional"))
      (node (ref "U2") (pin "28") (pinfunction "PB15_28") (pintype "bidirectional"))
    )
    (net (code "18") (name "NRST") (class "Default")
      (node (ref "C23") (pin "1") (pinfunction "1_1") (pintype "passive"))
      (node (ref "U2") (pin "7") (pinfunction "NRST_7") (pintype "bidirectional"))
    )
    (net (code "19") (name "Net-(D1-PadC)") (class "Default")
      (node (ref "D1") (pin "C") (pinfunction "C_C") (pintype "passive"))
      (node (ref "R1") (pin "2") (pinfunction "2_2") (pintype "passive"))
    )
    (net (code "20") (name "Net-(D2-PadC)") (class "Default")
      (node (ref "D2") (pin "C") (pinfunction "C_C") (pintype "passive"))
      (node (ref "R3") (pin "2") (pinfunction "2_2") (pintype "passive"))
    )
    (net (code "21") (name "Net-(D10-C)") (class "Default")
      (node (ref "C11") (pin "1") (pinfunction "1_1") (pintype "passive"))
      (node (ref "C2") (pin "+") (pinfunction "+_+") (pintype "passive"))
      (node (ref "D10") (pin "1") (pinfunction "C_1") (pintype "passive"))
      (node (ref "U15") (pin "3") (pinfunction "VIN_3") (pintype "input"))
    )
    (net (code "22") (name "Net-(D11-C)") (class "Default")
      (node (ref "C4") (pin "+") (pinfunction "+_+") (pintype "passive"))
      (node (ref "C9") (pin "1") (pinfunction "1_1") (pintype "passive"))
      (node (ref "D11") (pin "1") (pinfunction "C_1") (pintype "passive"))
      (node (ref "U16") (pin "3") (pinfunction "VIN_3") (pintype "input"))
    )
    (net (code "23") (name "Net-(D12-PadC)") (class "Default")
      (node (ref "D12") (pin "C") (pinfunction "C_C") (pintype "passive"))
      (node (ref "R39") (pin "2") (pinfunction "2_2") (pintype "passive"))
    )
    (net (code "24") (name "Net-(D13-PadA)") (class "Default")
      (node (ref "D13") (pin "A") (pinfunction "A_A") (pintype "passive"))
      (node (ref "R14") (pin "1") (pinfunction "1_1") (pintype "passive"))
    )
    (net (code "25") (name "Net-(D14-PadC)") (class "Default")
      (node (ref "D14") (pin "C") (pinfunction "C_C") (pintype "passive"))
      (node (ref "R18") (pin "2") (pinfunction "2_2") (pintype "passive"))
    )
    (net (code "26") (name "Net-(D15-PadC)") (class "Default")
      (node (ref "D15") (pin "C") (pinfunction "C_C") (pintype "passive"))
      (node (ref "R19") (pin "2") (pinfunction "2_2") (pintype "passive"))
    )
    (net (code "27") (name "Net-(D16-PadA)") (class "Default")
      (node (ref "D16") (pin "A") (pinfunction "A_A") (pintype "passive"))
      (node (ref "R13") (pin "1") (pinfunction "1_1") (pintype "passive"))
    )
    (net (code "28") (name "Net-(D17-PadA)") (class "Default")
      (node (ref "D17") (pin "A") (pinfunction "A_A") (pintype "passive"))
      (node (ref "R20") (pin "1") (pinfunction "1_1") (pintype "passive"))
    )
    (net (code "29") (name "Net-(J4-SIGNAL)") (class "Default")
      (node (ref "C16") (pin "1") (pinfunction "1_1") (pintype "passive"))
      (node (ref "J4") (pin "FEED") (pinfunction "SIGNAL_FEED") (pintype "bidirectional"))
      (node (ref "R4") (pin "1") (pinfunction "1_1") (pintype "passive"))
    )
    (net (code "30") (name "Net-(LS1-PadP)") (class "Default")
      (node (ref "LS1") (pin "P") (pinfunction "P_P") (pintype "passive"))
      (node (ref "R32") (pin "2") (pinfunction "2_2") (pintype "passive"))
    )
    (net (code "31") (name "Net-(POWER-Pad1)") (class "Default")
      (node (ref "POWER") (pin "1") (pinfunction "1_1") (pintype "passive"))
      (node (ref "SW2") (pin "2") (pinfunction "2_2") (pintype "passive"))
    )
    (net (code "32") (name "Net-(U13-1PPS)") (class "Default")
      (node (ref "R14") (pin "2") (pinfunction "2_2") (pintype "passive"))
      (node (ref "U13") (pin "6") (pinfunction "1PPS_6") (pintype "output"))
    )
    (net (code "33") (name "Net-(U13-AADET_N)") (class "Default")
      (node (ref "R13") (pin "2") (pinfunction "2_2") (pintype "passive"))
      (node (ref "U13") (pin "8") (pinfunction "AADET_N_8") (pintype "output"))
    )
    (net (code "34") (name "Net-(U13-FORCE_ON)") (class "Default")
      (node (ref "R11") (pin "2") (pinfunction "2_2") (pintype "passive"))
      (node (ref "R12") (pin "2") (pinfunction "2_2") (pintype "passive"))
      (node (ref "U13") (pin "7") (pinfunction "FORCE_ON_7") (pintype "input"))
    )
    (net (code "35") (name "Net-(U13-~{RESET})") (class "Default")
      (node (ref "R17") (pin "1") (pinfunction "1_1") (pintype "passive"))
      (node (ref "U13") (pin "10") (pinfunction "~{RESET}_10") (pintype "input"))
    )
    (net (code "36") (name "Net-(U15-VOUT)") (class "Default")
      (node (ref "C12") (pin "1") (pinfunction "1_1") (pintype "passive"))
      (node (ref "C3") (pin "+") (pinfunction "+_+") (pintype "passive"))
      (node (ref "F2") (pin "1") (pinfunction "1_1") (pintype "bidirectional"))
      (node (ref "U15") (pin "2") (pinfunction "VOUT_2") (pintype "output"))
    )
    (net (code "37") (name "Net-(U16-VOUT)") (class "Default")
      (node (ref "C10") (pin "1") (pinfunction "1_1") (pintype "passive"))
      (node (ref "C5") (pin "+") (pinfunction "+_+") (pintype "passive"))
      (node (ref "F4") (pin "1") (pinfunction "1_1") (pintype "bidirectional"))
      (node (ref "U16") (pin "2") (pinfunction "VOUT_2") (pintype "output"))
    )
    (net (code "38") (name "Net-(X1-ANT)") (class "Default")
      (node (ref "U14") (pin "ANT") (pinfunction "ANT_ANT") (pintype "bidirectional"))
      (node (ref "X1") (pin "ANTENNA") (pinfunction "ANT_ANTENNA") (pintype "bidirectional"))
    )
    (net (code "39") (name "OSC_IN") (class "Default")
      (node (ref "C15") (pin "2") (pinfunction "2_2") (pintype "passive"))
      (node (ref "U2") (pin "5") (pinfunction "OSC_IN_5") (pintype "input"))
      (node (ref "Y1") (pin "1") (pinfunction "1_1") (pintype "passive"))
    )
    (net (code "40") (name "OSC_OUT") (class "Default")
      (node (ref "C14") (pin "2") (pinfunction "2_2") (pintype "passive"))
      (node (ref "U2") (pin "6") (pinfunction "OSC_OUT_6") (pintype "output"))
      (node (ref "Y1") (pin "3") (pinfunction "3_3") (pintype "passive"))
    )
    (net (code "41") (name "RX1") (class "Default")
      (node (ref "U13") (pin "2") (pinfunction "TXD1_2") (pintype "output"))
      (node (ref "U2") (pin "31") (pinfunction "PA10_31") (pintype "bidirectional"))
    )
    (net (code "42") (name "RX2") (class "Default")
      (node (ref "U14") (pin "TX") (pinfunction "TXD_TX") (pintype "bidirectional"))
      (node (ref "U2") (pin "13") (pinfunction "PA3_13") (pintype "bidirectional"))
    )
    (net (code "43") (name "RX3") (class "Default")
      (node (ref "U2") (pin "22") (pinfunction "PB11_22") (pintype "bidirectional"))
      (node (ref "X2") (pin "3") (pinfunction "S_3") (pintype "passive"))
    )
    (net (code "44") (name "SCK") (class "Default")
      (node (ref "J2") (pin "5") (pinfunction "CLK(SCK)_5") (pintype "bidirectional"))
      (node (ref "U2") (pin "26") (pinfunction "PB13_26") (pintype "bidirectional"))
    )
    (net (code "45") (name "SCL") (class "Default")
      (node (ref "J3") (pin "3") (pinfunction "3_3") (pintype "passive"))
      (node (ref "U2") (pin "42") (pinfunction "PB6_42") (pintype "bidirectional"))
    )
    (net (code "46") (name "SDA") (class "Default")
      (node (ref "J3") (pin "2") (pinfunction "2_2") (pintype "passive"))
      (node (ref "U2") (pin "43") (pinfunction "PB7_43") (pintype "bidirectional"))
    )
    (net (code "47") (name "SWCLK") (class "Default")
      (node (ref "STM1") (pin "2") (pinfunction "2_2") (pintype "passive"))
      (node (ref "U2") (pin "37") (pinfunction "PA14_37") (pintype "bidirectional"))
    )
    (net (code "48") (name "SWDIO") (class "Default")
      (node (ref "STM1") (pin "3") (pinfunction "3_3") (pintype "passive"))
      (node (ref "U2") (pin "34") (pinfunction "PA13_34") (pintype "bidirectional"))
    )
    (net (code "49") (name "TX1") (class "Default")
      (node (ref "R15") (pin "1") (pinfunction "1_1") (pintype "passive"))
      (node (ref "U2") (pin "30") (pinfunction "PA9_30") (pintype "bidirectional"))
    )
    (net (code "50") (name "TX2") (class "Default")
      (node (ref "U14") (pin "RX") (pinfunction "RXD_RX") (pintype "bidirectional"))
      (node (ref "U2") (pin "12") (pinfunction "PA2_12") (pintype "bidirectional"))
    )
    (net (code "51") (name "TX3") (class "Default")
      (node (ref "U2") (pin "21") (pinfunction "PB10_21") (pintype "bidirectional"))
      (node (ref "X2") (pin "2") (pinfunction "S_2") (pintype "passive"))
    )
    (net (code "52") (name "TXD") (class "Default")
      (node (ref "R15") (pin "2") (pinfunction "2_2") (pintype "passive"))
      (node (ref "R16") (pin "2") (pinfunction "2_2") (pintype "passive"))
      (node (ref "U13") (pin "1") (pinfunction "RXD1_1") (pintype "input"))
    )
    (net (code "53") (name "USB_N") (class "Default")
      (node (ref "J5") (pin "D-1") (pinfunction "D-_D-1") (pintype "bidirectional"))
      (node (ref "U2") (pin "32") (pinfunction "PA11_32") (pintype "bidirectional"))
    )
    (net (code "54") (name "USB_P") (class "Default")
      (node (ref "J5") (pin "D+1") (pinfunction "D+_D+1") (pintype "bidirectional"))
      (node (ref "U2") (pin "33") (pinfunction "PA12_33") (pintype "bidirectional"))
    )
    (net (code "55") (name "VB") (class "Default")
      (node (ref "U2") (pin "16") (pinfunction "PA6_16") (pintype "bidirectional"))
      (node (ref "VBAT_D") (pin "2") (pinfunction "2_2") (pintype "passive"))
      (node (ref "VBAT_U") (pin "1") (pinfunction "1_1") (pintype "passive"))
    )
    (net (code "56") (name "VCC") (class "Default")
      (node (ref "D10") (pin "2") (pinfunction "A_2") (pintype "passive"))
      (node (ref "D11") (pin "2") (pinfunction "A_2") (pintype "passive"))
      (node (ref "SW2") (pin "1") (pinfunction "1_1") (pintype "passive"))
      (node (ref "VBAT_U") (pin "2") (pinfunction "2_2") (pintype "passive"))
    )
    (net (code "57") (name "VDDA") (class "Default")
      (node (ref "L2") (pin "2") (pinfunction "2_2") (pintype "passive"))
      (node (ref "U2") (pin "9") (pinfunction "VDDA_9") (pintype "power_in"))
      (node (ref "VDDA3") (pin "1") (pinfunction "1_1") (pintype "passive"))
      (node (ref "VDDA4") (pin "1") (pinfunction "1_1") (pintype "passive"))
    )
    (net (code "58") (name "V_BCKP") (class "Default")
      (node (ref "B1") (pin "+") (pinfunction "+_+") (pintype "power_in"))
      (node (ref "C24") (pin "1") (pinfunction "1_1") (pintype "passive"))
      (node (ref "C26") (pin "+") (pinfunction "+_+") (pintype "passive"))
      (node (ref "R39") (pin "1") (pinfunction "1_1") (pintype "passive"))
      (node (ref "U13") (pin "5") (pinfunction "V_BCKP_5") (pintype "power_in"))
    )
    (net (code "59") (name "XANT") (class "Default")
      (node (ref "C17") (pin "1") (pinfunction "1_1") (pintype "passive"))
      (node (ref "R4") (pin "2") (pinfunction "2_2") (pintype "passive"))
      (node (ref "U13") (pin "11") (pinfunction "EX_ANT_11") (pintype "input"))
    )
    (net (code "60") (name "unconnected-(J2B-DAT1(RSV)-Pad8)") (class "Default")
      (node (ref "J2") (pin "8") (pinfunction "DAT1(RSV)_8") (pintype "bidirectional"))
    )
    (net (code "61") (name "unconnected-(J2B-DAT2(NC)-Pad1)") (class "Default")
      (node (ref "J2") (pin "1") (pinfunction "DAT2(NC)_1") (pintype "bidirectional"))
    )
    (net (code "62") (name "unconnected-(J5-USBID-PadID1)") (class "Default")
      (node (ref "J5") (pin "ID1") (pinfunction "USBID_ID1") (pintype "bidirectional"))
    )
    (net (code "63") (name "unconnected-(U2A-PA4-Pad14)") (class "Default")
      (node (ref "U2") (pin "14") (pinfunction "PA4_14") (pintype "bidirectional"))
    )
    (net (code "64") (name "unconnected-(U2A-PA15-Pad38)") (class "Default")
      (node (ref "U2") (pin "38") (pinfunction "PA15_38") (pintype "bidirectional"))
    )
    (net (code "65") (name "unconnected-(U2A-PB1-Pad19)") (class "Default")
      (node (ref "U2") (pin "19") (pinfunction "PB1_19") (pintype "bidirectional"))
    )
    (net (code "66") (name "unconnected-(U2A-PB2-Pad20)") (class "Default")
      (node (ref "U2") (pin "20") (pinfunction "PB2_20") (pintype "bidirectional"))
    )
    (net (code "67") (name "unconnected-(U2A-PB3-Pad39)") (class "Default")
      (node (ref "U2") (pin "39") (pinfunction "PB3_39") (pintype "bidirectional"))
    )
    (net (code "68") (name "unconnected-(U2A-PB8-Pad45)") (class "Default")
      (node (ref "U2") (pin "45") (pinfunction "PB8_45") (pintype "bidirectional"))
    )
    (net (code "69") (name "unconnected-(U2A-PB9-Pad46)") (class "Default")
      (node (ref "U2") (pin "46") (pinfunction "PB9_46") (pintype "bidirectional"))
    )
    (net (code "70") (name "unconnected-(U2A-PC13-Pad2)") (class "Default")
      (node (ref "U2") (pin "2") (pinfunction "PC13_2") (pintype "bidirectional"))
    )
    (net (code "71") (name "unconnected-(U2A-PC14-OSC32_IN-Pad3)") (class "Default")
      (node (ref "U2") (pin "3") (pinfunction "PC14-OSC32_IN_3") (pintype "bidirectional"))
    )
    (net (code "72") (name "unconnected-(U2A-PC15-OSC32_OUT-Pad4)") (class "Default")
      (node (ref "U2") (pin "4") (pinfunction "PC15-OSC32_OUT_4") (pintype "bidirectional"))
    )
    (net (code "73") (name "unconnected-(U14-Pad3V3)") (class "Default")
      (node (ref "U14") (pin "3V3") (pinfunction "3V3_3V3") (pintype "bidirectional"))
    )
    (net (code "74") (name "unconnected-(U14-PadPB0)") (class "Default")
      (node (ref "U14") (pin "PB0") (pinfunction "PB0_PB0") (pintype "bidirectional"))
    )
    (net (code "75") (name "unconnected-(U14-PadPB1)") (class "Default")
      (node (ref "U14") (pin "PB1") (pinfunction "PB1_PB1") (pintype "bidirectional"))
    )
    (net (code "76") (name "unconnected-(U14-PadPB3)") (class "Default")
      (node (ref "U14") (pin "PB3") (pinfunction "PB3_PB3") (pintype "bidirectional"))
    )
    (net (code "77") (name "unconnected-(U14-PadRST)") (class "Default")
      (node (ref "U14") (pin "RST") (pinfunction "RST_RST") (pintype "bidirectional"))
    )
    (net (code "78") (name "unconnected-(U14-PadSWIM)") (class "Default")
      (node (ref "U14") (pin "SWIM") (pinfunction "SWIM_SWIM") (pintype "bidirectional"))
    )
  )
)
